# Sheet1-nano.net
KiCad netlist of a schematic drawn in Altium Designer
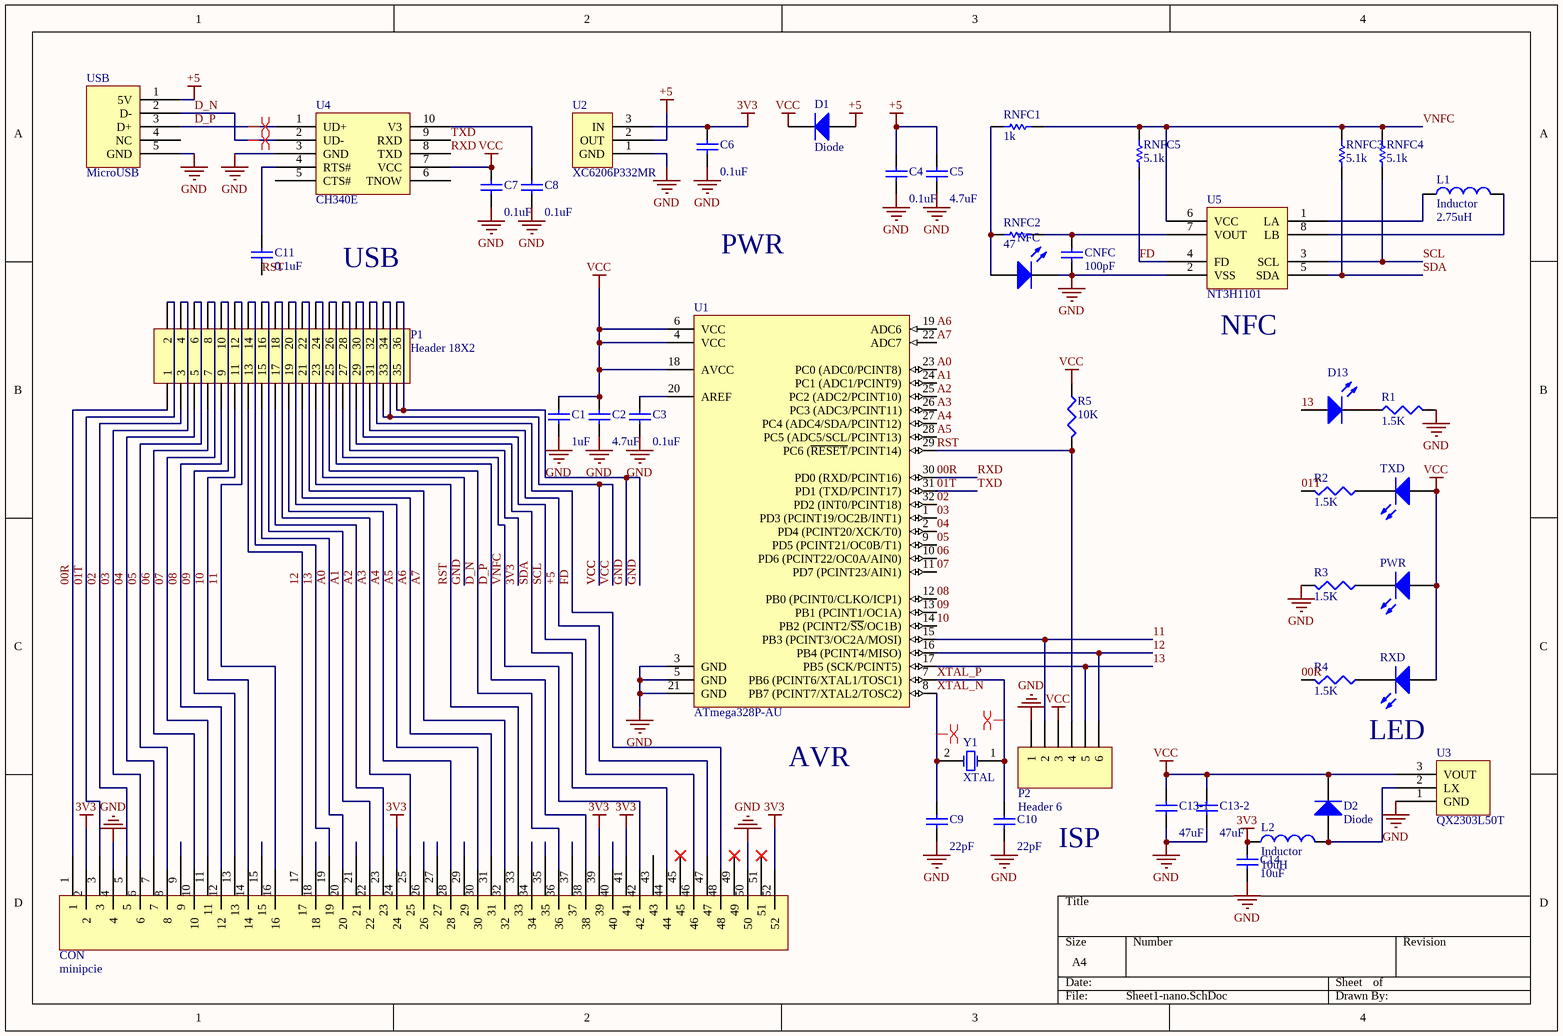
[diagram p0: Sheet1-nano.SchDoc]

(export (version "E")
  (design (tool "Eeschema 10.0.6"))
  (components
    (comp (ref "C1")
      (value "1uF")
      (footprint "0603C")
      (description "Capacitor")
      (fields (field (name "Comment") "Cap") (field (name "PUBLISHER") "Altium Limited"))
      (libsource (lib "Miscellaneous Devices") (part "Cap"))
    )
    (comp (ref "C2")
      (value "4.7uF")
      (footprint "0603C")
      (description "Capacitor")
      (fields (field (name "Comment") "Cap") (field (name "PUBLISHER") "Altium Limited"))
      (libsource (lib "Miscellaneous Devices") (part "Cap"))
    )
    (comp (ref "C3")
      (value "0.1uF")
      (footprint "0603C")
      (description "Capacitor")
      (fields (field (name "Comment") "Cap") (field (name "PUBLISHER") "Altium Limited"))
      (libsource (lib "Miscellaneous Devices") (part "Cap"))
    )
    (comp (ref "C4")
      (value "0.1uF")
      (footprint "0603C")
      (description "Capacitor")
      (fields (field (name "Comment") "Cap") (field (name "PUBLISHER") "Altium Limited"))
      (libsource (lib "Miscellaneous Devices") (part "Cap"))
    )
    (comp (ref "C5")
      (value "4.7uF")
      (footprint "0603C")
      (description "Capacitor")
      (fields (field (name "Comment") "Cap") (field (name "PUBLISHER") "Altium Limited"))
      (libsource (lib "Miscellaneous Devices") (part "Cap"))
    )
    (comp (ref "C6")
      (value "0.1uF")
      (footprint "0603C")
      (description "Capacitor")
      (fields (field (name "Comment") "Cap") (field (name "PUBLISHER") "Altium Limited"))
      (libsource (lib "Miscellaneous Devices") (part "Cap"))
    )
    (comp (ref "C7")
      (value "0.1uF")
      (footprint "0603C")
      (description "Capacitor")
      (fields (field (name "Comment") "Cap") (field (name "PUBLISHER") "Altium Limited"))
      (libsource (lib "Miscellaneous Devices") (part "Cap"))
    )
    (comp (ref "C8")
      (value "0.1uF")
      (footprint "0603C")
      (description "Capacitor")
      (fields (field (name "Comment") "Cap") (field (name "PUBLISHER") "Altium Limited"))
      (libsource (lib "Miscellaneous Devices") (part "Cap"))
    )
    (comp (ref "C9")
      (value "22pF")
      (footprint "0603C")
      (description "Capacitor")
      (fields (field (name "Comment") "Cap") (field (name "PUBLISHER") "Altium Limited"))
      (libsource (lib "Miscellaneous Devices") (part "Cap"))
    )
    (comp (ref "C10")
      (value "22pF")
      (footprint "0603C")
      (description "Capacitor")
      (fields (field (name "Comment") "Cap") (field (name "PUBLISHER") "Altium Limited"))
      (libsource (lib "Miscellaneous Devices") (part "Cap"))
    )
    (comp (ref "C11")
      (value "0.1uF")
      (footprint "0603C")
      (description "Capacitor")
      (fields (field (name "Comment") "Cap") (field (name "PUBLISHER") "Altium Limited"))
      (libsource (lib "Miscellaneous Devices") (part "Cap"))
    )
    (comp (ref "C13-1")
      (value "47uF")
      (footprint "0603C")
      (description "Capacitor")
      (fields (field (name "Comment") "Cap") (field (name "PUBLISHER") "Altium Limited"))
      (libsource (lib "Miscellaneous Devices") (part "Cap"))
    )
    (comp (ref "C13-2")
      (value "47uF")
      (footprint "0603C")
      (description "Capacitor")
      (fields (field (name "Comment") "Cap") (field (name "PUBLISHER") "Altium Limited"))
      (libsource (lib "Miscellaneous Devices") (part "Cap"))
    )
    (comp (ref "C14")
      (value "10uF")
      (footprint "0603C")
      (description "Capacitor")
      (fields (field (name "Comment") "Cap") (field (name "PUBLISHER") "Altium Limited"))
      (libsource (lib "Miscellaneous Devices") (part "Cap"))
    )
    (comp (ref "CNFC")
      (value "100pF")
      (footprint "0603C")
      (description "Capacitor")
      (fields (field (name "Comment") "Cap") (field (name "PUBLISHER") "Altium Limited"))
      (libsource (lib "Miscellaneous Devices") (part "Cap"))
    )
    (comp (ref "CON")
      (value "minipcie")
      (footprint "MINI PCI E PADS")
      (libsource (lib "Custom") (part "minipcie"))
    )
    (comp (ref "D1")
      (value "Diode")
      (footprint "1206Led")
      (description "Default Diode")
      (fields (field (name "PUBLISHER") "Altium Limited"))
      (libsource (lib "Miscellaneous Devices") (part "Diode"))
    )
    (comp (ref "D2")
      (value "Diode")
      (footprint "1206Led")
      (description "Default Diode")
      (fields (field (name "PUBLISHER") "Altium Limited"))
      (libsource (lib "Miscellaneous Devices") (part "Diode"))
    )
    (comp (ref "D13")
      (value "LED0")
      (footprint "24LIB 3D pcbModel :0805LED2")
      (description "Typical INFRARED GaAs LED")
      (fields (field (name "PUBLISHER") "Altium Limited"))
      (libsource (lib "Miscellaneous Devices") (part "LED0"))
    )
    (comp (ref "L1")
      (value "Inductor")
      (footprint "L-2.75uH")
      (fields (field (name "ALTIUM_VALUE") "2.75uH") (field (name "PUBLISHER") "Altium Limited"))
      (libsource (lib "Miscellaneous Devices") (part "Inductor"))
    )
    (comp (ref "L2")
      (value "Inductor")
      (footprint "0603c")
      (fields (field (name "ALTIUM_VALUE") "10uH") (field (name "PUBLISHER") "Altium Limited"))
      (libsource (lib "Miscellaneous Devices") (part "Inductor"))
    )
    (comp (ref "NFC")
      (value "LED1")
      (footprint "0805LED2")
      (description "Typical RED GaAs LED")
      (fields (field (name "PUBLISHER") "Altium Limited"))
      (libsource (lib "Miscellaneous Devices") (part "LED1"))
    )
    (comp (ref "P1")
      (value "Header 18X2")
      (footprint "HDR2X18")
      (description "Header, 18-Pin, Dual row")
      (fields (field (name "PUBLISHER") "Altium Limited"))
      (libsource (lib "Miscellaneous Connectors") (part "Header 18X2"))
    )
    (comp (ref "P2")
      (value "Header 6")
      (footprint "HDR1X6")
      (description "Header, 6-Pin")
      (fields (field (name "PUBLISHER") "Altium Limited"))
      (libsource (lib "Miscellaneous Connectors") (part "Header 6"))
    )
    (comp (ref "PWR")
      (value "LED0")
      (footprint "24LIB 3D pcbModel :0805LED2")
      (description "Typical INFRARED GaAs LED")
      (fields (field (name "PUBLISHER") "Altium Limited"))
      (libsource (lib "Miscellaneous Devices") (part "LED0"))
    )
    (comp (ref "R1")
      (value "1.5K")
      (footprint "0805-1R")
      (description "Resistor")
      (fields (field (name "Comment") "Res3") (field (name "PUBLISHER") "Altium Limited"))
      (libsource (lib "Miscellaneous Devices") (part "Res3"))
    )
    (comp (ref "R2")
      (value "1.5K")
      (footprint "0805-1R")
      (description "Resistor")
      (fields (field (name "Comment") "Res3") (field (name "PUBLISHER") "Altium Limited"))
      (libsource (lib "Miscellaneous Devices") (part "Res3"))
    )
    (comp (ref "R3")
      (value "1.5K")
      (footprint "0805-1R")
      (description "Resistor")
      (fields (field (name "Comment") "Res3") (field (name "PUBLISHER") "Altium Limited"))
      (libsource (lib "Miscellaneous Devices") (part "Res3"))
    )
    (comp (ref "R4")
      (value "1.5K")
      (footprint "0805-1R")
      (description "Resistor")
      (fields (field (name "Comment") "Res3") (field (name "PUBLISHER") "Altium Limited"))
      (libsource (lib "Miscellaneous Devices") (part "Res3"))
    )
    (comp (ref "R5")
      (value "10K")
      (footprint "0805-1R")
      (description "Resistor")
      (fields (field (name "Comment") "Res3") (field (name "PUBLISHER") "Altium Limited"))
      (libsource (lib "Miscellaneous Devices") (part "Res3"))
    )
    (comp (ref "RNFC1")
      (value "1k")
      (footprint "0805-1R")
      (description "Resistor")
      (fields (field (name "Comment") "Res1") (field (name "PUBLISHER") "Altium Limited"))
      (libsource (lib "Miscellaneous Devices") (part "Res1"))
    )
    (comp (ref "RNFC2")
      (value "47")
      (footprint "0805-1R")
      (description "Resistor")
      (fields (field (name "Comment") "Res1") (field (name "PUBLISHER") "Altium Limited"))
      (libsource (lib "Miscellaneous Devices") (part "Res1"))
    )
    (comp (ref "RNFC3")
      (value "5.1k")
      (footprint "0805-1R")
      (description "Resistor")
      (fields (field (name "Comment") "Res1") (field (name "PUBLISHER") "Altium Limited"))
      (libsource (lib "Miscellaneous Devices") (part "Res1"))
    )
    (comp (ref "RNFC4")
      (value "5.1k")
      (footprint "0805-1R")
      (description "Resistor")
      (fields (field (name "Comment") "Res1") (field (name "PUBLISHER") "Altium Limited"))
      (libsource (lib "Miscellaneous Devices") (part "Res1"))
    )
    (comp (ref "RNFC5")
      (value "5.1k")
      (footprint "0805-1R")
      (description "Resistor")
      (fields (field (name "Comment") "Res1") (field (name "PUBLISHER") "Altium Limited"))
      (libsource (lib "Miscellaneous Devices") (part "Res1"))
    )
    (comp (ref "RXD")
      (value "LED0")
      (footprint "24LIB 3D pcbModel :0805LED2")
      (description "Typical INFRARED GaAs LED")
      (fields (field (name "PUBLISHER") "Altium Limited"))
      (libsource (lib "Miscellaneous Devices") (part "LED0"))
    )
    (comp (ref "TXD")
      (value "LED0")
      (footprint "24LIB 3D pcbModel :0805LED2")
      (description "Typical INFRARED GaAs LED")
      (fields (field (name "PUBLISHER") "Altium Limited"))
      (libsource (lib "Miscellaneous Devices") (part "LED0"))
    )
    (comp (ref "U1")
      (value "ATmega328P-AU")
      (footprint "32A_N")
      (fields (field (name "PUBLISHER") "Altium Limited"))
      (libsource (lib "Atmel Microcontroller 8-Bit megaAVR") (part "ATmega328P-AU"))
    )
    (comp (ref "U2") (value "XC6206P332MR") (footprint "SOT-23") (libsource (lib "Custom") (part "AMS1117")))
    (comp (ref "U3") (value "QX2303L50T") (footprint "sot23") (libsource (lib "Custom") (part "QX2303L50T")))
    (comp (ref "U4") (value "CH340E") (footprint "MS10") (libsource (lib "Custom") (part "CH340E")))
    (comp (ref "U5")
      (value "NT3H1101")
      (footprint "XQFN-8_L1.6-W1.6-P0.50-BL")
      (libsource (lib "IDCARD") (part "NT3H1101"))
    )
    (comp (ref "USB")
      (value "MicroUSB")
      (footprint "MicroUSB-InBoard")
      (libsource (lib "Custom") (part "MicroUSB"))
    )
    (comp (ref "Y1")
      (value "XTAL")
      (footprint "SMD-3225")
      (description "Crystal Oscillator")
      (fields (field (name "PUBLISHER") "Altium Limited"))
      (libsource (lib "Miscellaneous Devices") (part "XTAL"))
    )
  )
  (nets
    (net (code "1") (name "+5") (class "Default")
      (node (ref "C4") (pin "2") (pinfunction "2_2") (pintype "passive"))
      (node (ref "C5") (pin "2") (pinfunction "2_2") (pintype "passive"))
      (node (ref "CON") (pin "47") (pinfunction "47_47") (pintype "passive"))
      (node (ref "D1") (pin "1") (pinfunction "A_1") (pintype "passive"))
      (node (ref "P1") (pin "31") (pinfunction "31_31") (pintype "passive"))
      (node (ref "U2") (pin "2") (pinfunction "OUT_2") (pintype "passive"))
      (node (ref "USB") (pin "1") (pinfunction "5V_1") (pintype "passive"))
    )
    (net (code "2") (name "/00R") (class "Default")
      (node (ref "CON") (pin "1") (pinfunction "1_1") (pintype "passive"))
      (node (ref "P1") (pin "1") (pinfunction "1_1") (pintype "passive"))
      (node (ref "R4") (pin "2") (pinfunction "2_2") (pintype "passive"))
      (node (ref "U1") (pin "30") (pinfunction "PD0_(RXD/PCINT16)_30") (pintype "bidirectional"))
      (node (ref "U4") (pin "8") (pinfunction "TXD_8") (pintype "passive"))
    )
    (net (code "3") (name "/01T") (class "Default")
      (node (ref "CON") (pin "3") (pinfunction "3_3") (pintype "passive"))
      (node (ref "P1") (pin "2") (pinfunction "2_2") (pintype "passive"))
      (node (ref "R2") (pin "2") (pinfunction "2_2") (pintype "passive"))
      (node (ref "U1") (pin "31") (pinfunction "PD1_(TXD/PCINT17)_31") (pintype "bidirectional"))
      (node (ref "U4") (pin "9") (pinfunction "RXD_9") (pintype "passive"))
    )
    (net (code "4") (name "/02") (class "Default")
      (node (ref "CON") (pin "5") (pinfunction "5_5") (pintype "passive"))
      (node (ref "P1") (pin "3") (pinfunction "3_3") (pintype "passive"))
      (node (ref "U1") (pin "32") (pinfunction "PD2_(INT0/PCINT18)_32") (pintype "bidirectional"))
    )
    (net (code "5") (name "/03") (class "Default")
      (node (ref "CON") (pin "6") (pinfunction "6_6") (pintype "passive"))
      (node (ref "P1") (pin "4") (pinfunction "4_4") (pintype "passive"))
      (node (ref "U1") (pin "1") (pinfunction "PD3_(PCINT19/OC2B/INT1)_1") (pintype "bidirectional"))
    )
    (net (code "6") (name "/04") (class "Default")
      (node (ref "CON") (pin "7") (pinfunction "7_7") (pintype "passive"))
      (node (ref "P1") (pin "5") (pinfunction "5_5") (pintype "passive"))
      (node (ref "U1") (pin "2") (pinfunction "PD4_(PCINT20/XCK/T0)_2") (pintype "bidirectional"))
    )
    (net (code "7") (name "/05") (class "Default")
      (node (ref "CON") (pin "8") (pinfunction "8_8") (pintype "passive"))
      (node (ref "P1") (pin "6") (pinfunction "6_6") (pintype "passive"))
      (node (ref "U1") (pin "9") (pinfunction "PD5_(PCINT21/OC0B/T1)_9") (pintype "bidirectional"))
    )
    (net (code "8") (name "/06") (class "Default")
      (node (ref "CON") (pin "10") (pinfunction "10_10") (pintype "passive"))
      (node (ref "P1") (pin "7") (pinfunction "7_7") (pintype "passive"))
      (node (ref "U1") (pin "10") (pinfunction "PD6_(PCINT22/OC0A/AIN0)_10") (pintype "bidirectional"))
    )
    (net (code "9") (name "/07") (class "Default")
      (node (ref "CON") (pin "11") (pinfunction "11_11") (pintype "passive"))
      (node (ref "P1") (pin "8") (pinfunction "8_8") (pintype "passive"))
      (node (ref "U1") (pin "11") (pinfunction "PD7_(PCINT23/AIN1)_11") (pintype "bidirectional"))
    )
    (net (code "10") (name "/08") (class "Default")
      (node (ref "CON") (pin "12") (pinfunction "12_12") (pintype "passive"))
      (node (ref "P1") (pin "9") (pinfunction "9_9") (pintype "passive"))
      (node (ref "U1") (pin "12") (pinfunction "PB0_(PCINT0/CLKO/ICP1)_12") (pintype "bidirectional"))
    )
    (net (code "11") (name "/09") (class "Default")
      (node (ref "CON") (pin "13") (pinfunction "13_13") (pintype "passive"))
      (node (ref "P1") (pin "10") (pinfunction "10_10") (pintype "passive"))
      (node (ref "U1") (pin "13") (pinfunction "PB1_(PCINT1/OC1A)_13") (pintype "bidirectional"))
    )
    (net (code "12") (name "/10") (class "Default")
      (node (ref "CON") (pin "14") (pinfunction "14_14") (pintype "passive"))
      (node (ref "P1") (pin "11") (pinfunction "11_11") (pintype "passive"))
      (node (ref "U1") (pin "14") (pinfunction "PB2_(PCINT2/~{SS}/OC1B)_14") (pintype "bidirectional"))
    )
    (net (code "13") (name "/11") (class "Default")
      (node (ref "CON") (pin "16") (pinfunction "16_16") (pintype "passive"))
      (node (ref "P1") (pin "12") (pinfunction "12_12") (pintype "passive"))
      (node (ref "P2") (pin "2") (pinfunction "2_2") (pintype "passive"))
      (node (ref "U1") (pin "15") (pinfunction "PB3_(PCINT3/OC2A/MOSI)_15") (pintype "bidirectional"))
    )
    (net (code "14") (name "/12") (class "Default")
      (node (ref "CON") (pin "17") (pinfunction "17_17") (pintype "passive"))
      (node (ref "P1") (pin "13") (pinfunction "13_13") (pintype "passive"))
      (node (ref "P2") (pin "6") (pinfunction "6_6") (pintype "passive"))
      (node (ref "U1") (pin "16") (pinfunction "PB4_(PCINT4/MISO)_16") (pintype "bidirectional"))
    )
    (net (code "15") (name "/13") (class "Default")
      (node (ref "CON") (pin "19") (pinfunction "19_19") (pintype "passive"))
      (node (ref "D13") (pin "1") (pinfunction "A_1") (pintype "passive"))
      (node (ref "P1") (pin "14") (pinfunction "14_14") (pintype "passive"))
      (node (ref "P2") (pin "5") (pinfunction "5_5") (pintype "passive"))
      (node (ref "U1") (pin "17") (pinfunction "PB5_(SCK/PCINT5)_17") (pintype "bidirectional"))
    )
    (net (code "16") (name "/A0") (class "Default")
      (node (ref "CON") (pin "20") (pinfunction "20_20") (pintype "passive"))
      (node (ref "P1") (pin "15") (pinfunction "15_15") (pintype "passive"))
      (node (ref "U1") (pin "23") (pinfunction "PC0_(ADC0/PCINT8)_23") (pintype "bidirectional"))
    )
    (net (code "17") (name "/A1") (class "Default")
      (node (ref "CON") (pin "22") (pinfunction "22_22") (pintype "passive"))
      (node (ref "P1") (pin "16") (pinfunction "16_16") (pintype "passive"))
      (node (ref "U1") (pin "24") (pinfunction "PC1_(ADC1/PCINT9)_24") (pintype "bidirectional"))
    )
    (net (code "18") (name "/A2") (class "Default")
      (node (ref "CON") (pin "23") (pinfunction "23_23") (pintype "passive"))
      (node (ref "P1") (pin "17") (pinfunction "17_17") (pintype "passive"))
      (node (ref "U1") (pin "25") (pinfunction "PC2_(ADC2/PCINT10)_25") (pintype "bidirectional"))
    )
    (net (code "19") (name "/A3") (class "Default")
      (node (ref "CON") (pin "25") (pinfunction "25_25") (pintype "passive"))
      (node (ref "P1") (pin "18") (pinfunction "18_18") (pintype "passive"))
      (node (ref "U1") (pin "26") (pinfunction "PC3_(ADC3/PCINT11)_26") (pintype "bidirectional"))
    )
    (net (code "20") (name "/A4") (class "Default")
      (node (ref "CON") (pin "28") (pinfunction "28_28") (pintype "passive"))
      (node (ref "P1") (pin "19") (pinfunction "19_19") (pintype "passive"))
      (node (ref "U1") (pin "27") (pinfunction "PC4_(ADC4/SDA/PCINT12)_27") (pintype "bidirectional"))
    )
    (net (code "21") (name "/A5") (class "Default")
      (node (ref "CON") (pin "30") (pinfunction "30_30") (pintype "passive"))
      (node (ref "P1") (pin "20") (pinfunction "20_20") (pintype "passive"))
      (node (ref "U1") (pin "28") (pinfunction "PC5_(ADC5/SCL/PCINT13)_28") (pintype "bidirectional"))
    )
    (net (code "22") (name "/A6") (class "Default")
      (node (ref "CON") (pin "31") (pinfunction "31_31") (pintype "passive"))
      (node (ref "P1") (pin "21") (pinfunction "21_21") (pintype "passive"))
      (node (ref "U1") (pin "19") (pinfunction "ADC6_19") (pintype "input"))
    )
    (net (code "23") (name "/A7") (class "Default")
      (node (ref "CON") (pin "32") (pinfunction "32_32") (pintype "passive"))
      (node (ref "P1") (pin "22") (pinfunction "22_22") (pintype "passive"))
      (node (ref "U1") (pin "22") (pinfunction "ADC7_22") (pintype "input"))
    )
    (net (code "24") (name "/D_N") (class "Default")
      (node (ref "CON") (pin "36") (pinfunction "36_36") (pintype "passive"))
      (node (ref "P1") (pin "25") (pinfunction "25_25") (pintype "passive"))
      (node (ref "U4") (pin "2") (pinfunction "UD-_2") (pintype "passive"))
      (node (ref "USB") (pin "2") (pinfunction "D-_2") (pintype "passive"))
    )
    (net (code "25") (name "/D_P") (class "Default")
      (node (ref "CON") (pin "38") (pinfunction "38_38") (pintype "passive"))
      (node (ref "P1") (pin "26") (pinfunction "26_26") (pintype "passive"))
      (node (ref "U4") (pin "1") (pinfunction "UD+_1") (pintype "passive"))
      (node (ref "USB") (pin "3") (pinfunction "D+_3") (pintype "passive"))
    )
    (net (code "26") (name "/FD") (class "Default")
      (node (ref "CON") (pin "48") (pinfunction "48_48") (pintype "passive"))
      (node (ref "P1") (pin "32") (pinfunction "32_32") (pintype "passive"))
      (node (ref "RNFC5") (pin "1") (pinfunction "1_1") (pintype "passive"))
      (node (ref "U5") (pin "4") (pinfunction "FD_4") (pintype "passive"))
    )
    (net (code "27") (name "/RST") (class "Default")
      (node (ref "C11") (pin "1") (pinfunction "1_1") (pintype "passive"))
      (node (ref "CON") (pin "33") (pinfunction "33_33") (pintype "passive"))
      (node (ref "P1") (pin "23") (pinfunction "23_23") (pintype "passive"))
      (node (ref "P2") (pin "4") (pinfunction "4_4") (pintype "passive"))
      (node (ref "R5") (pin "2") (pinfunction "2_2") (pintype "passive"))
      (node (ref "U1") (pin "29") (pinfunction "PC6_(~{RESET}/PCINT14)_29") (pintype "bidirectional"))
    )
    (net (code "28") (name "/SCL") (class "Default")
      (node (ref "CON") (pin "46") (pinfunction "46_46") (pintype "passive"))
      (node (ref "P1") (pin "30") (pinfunction "30_30") (pintype "passive"))
      (node (ref "RNFC4") (pin "1") (pinfunction "1_1") (pintype "passive"))
      (node (ref "U5") (pin "3") (pinfunction "SCL_3") (pintype "passive"))
    )
    (net (code "29") (name "/SDA") (class "Default")
      (node (ref "CON") (pin "44") (pinfunction "44_44") (pintype "passive"))
      (node (ref "P1") (pin "29") (pinfunction "29_29") (pintype "passive"))
      (node (ref "RNFC3") (pin "1") (pinfunction "1_1") (pintype "passive"))
      (node (ref "U5") (pin "5") (pinfunction "SDA_5") (pintype "passive"))
    )
    (net (code "30") (name "/VNFC") (class "Default")
      (node (ref "CON") (pin "42") (pinfunction "42_42") (pintype "passive"))
      (node (ref "P1") (pin "27") (pinfunction "27_27") (pintype "passive"))
      (node (ref "RNFC1") (pin "2") (pinfunction "2_2") (pintype "passive"))
      (node (ref "RNFC3") (pin "2") (pinfunction "2_2") (pintype "passive"))
      (node (ref "RNFC4") (pin "2") (pinfunction "2_2") (pintype "passive"))
      (node (ref "RNFC5") (pin "2") (pinfunction "2_2") (pintype "passive"))
      (node (ref "U5") (pin "6") (pinfunction "VCC_6") (pintype "passive"))
    )
    (net (code "31") (name "/XTAL_N") (class "Default")
      (node (ref "C9") (pin "2") (pinfunction "2_2") (pintype "passive"))
      (node (ref "U1") (pin "8") (pinfunction "PB7_(PCINT7/XTAL2/TOSC2)_8") (pintype "bidirectional"))
      (node (ref "Y1") (pin "2") (pinfunction "OSC2_2") (pintype "passive"))
    )
    (net (code "32") (name "/XTAL_P") (class "Default")
      (node (ref "C10") (pin "2") (pinfunction "2_2") (pintype "passive"))
      (node (ref "U1") (pin "7") (pinfunction "PB6_(PCINT6/XTAL1/TOSC1)_7") (pintype "bidirectional"))
      (node (ref "Y1") (pin "1") (pinfunction "OSC1_1") (pintype "passive"))
    )
    (net (code "33") (name "3V3") (class "Default")
      (node (ref "C14") (pin "1") (pinfunction "1_1") (pintype "passive"))
      (node (ref "C6") (pin "2") (pinfunction "2_2") (pintype "passive"))
      (node (ref "CON") (pin "2") (pinfunction "2_2") (pintype "passive"))
      (node (ref "CON") (pin "24") (pinfunction "24_24") (pintype "passive"))
      (node (ref "CON") (pin "39") (pinfunction "39_39") (pintype "passive"))
      (node (ref "CON") (pin "41") (pinfunction "41_41") (pintype "passive"))
      (node (ref "CON") (pin "52") (pinfunction "52_52") (pintype "passive"))
      (node (ref "L2") (pin "1") (pinfunction "1_1") (pintype "passive"))
      (node (ref "P1") (pin "28") (pinfunction "28_28") (pintype "passive"))
      (node (ref "U2") (pin "3") (pinfunction "IN_3") (pintype "passive"))
    )
    (net (code "34") (name "GND") (class "Default")
      (node (ref "C1") (pin "1") (pinfunction "1_1") (pintype "passive"))
      (node (ref "C10") (pin "1") (pinfunction "1_1") (pintype "passive"))
      (node (ref "C13-1") (pin "1") (pinfunction "1_1") (pintype "passive"))
      (node (ref "C13-2") (pin "1") (pinfunction "1_1") (pintype "passive"))
      (node (ref "C14") (pin "2") (pinfunction "2_2") (pintype "passive"))
      (node (ref "C2") (pin "1") (pinfunction "1_1") (pintype "passive"))
      (node (ref "C3") (pin "1") (pinfunction "1_1") (pintype "passive"))
      (node (ref "C4") (pin "1") (pinfunction "1_1") (pintype "passive"))
      (node (ref "C5") (pin "1") (pinfunction "1_1") (pintype "passive"))
      (node (ref "C6") (pin "1") (pinfunction "1_1") (pintype "passive"))
      (node (ref "C7") (pin "1") (pinfunction "1_1") (pintype "passive"))
      (node (ref "C8") (pin "1") (pinfunction "1_1") (pintype "passive"))
      (node (ref "C9") (pin "1") (pinfunction "1_1") (pintype "passive"))
      (node (ref "CNFC") (pin "1") (pinfunction "1_1") (pintype "passive"))
      (node (ref "CON") (pin "4") (pinfunction "4_4") (pintype "passive"))
      (node (ref "CON") (pin "50") (pinfunction "50_50") (pintype "passive"))
      (node (ref "NFC") (pin "2") (pinfunction "K_2") (pintype "passive"))
      (node (ref "P1") (pin "24") (pinfunction "24_24") (pintype "passive"))
      (node (ref "P1") (pin "35") (pinfunction "35_35") (pintype "passive"))
      (node (ref "P1") (pin "36") (pinfunction "36_36") (pintype "passive"))
      (node (ref "P2") (pin "1") (pinfunction "1_1") (pintype "passive"))
      (node (ref "R1") (pin "2") (pinfunction "2_2") (pintype "passive"))
      (node (ref "R3") (pin "2") (pinfunction "2_2") (pintype "passive"))
      (node (ref "U1") (pin "21") (pinfunction "GND_21") (pintype "power_in"))
      (node (ref "U1") (pin "3") (pinfunction "GND_3") (pintype "power_in"))
      (node (ref "U1") (pin "5") (pinfunction "GND_5") (pintype "power_in"))
      (node (ref "U2") (pin "1") (pinfunction "GND_1") (pintype "passive"))
      (node (ref "U3") (pin "1") (pinfunction "GND_1") (pintype "passive"))
      (node (ref "U4") (pin "3") (pinfunction "GND_3") (pintype "passive"))
      (node (ref "U5") (pin "2") (pinfunction "VSS_2") (pintype "passive"))
      (node (ref "USB") (pin "5") (pinfunction "GND_5") (pintype "passive"))
    )
    (net (code "35") (name "Net-(D2-A)") (class "Default")
      (node (ref "D2") (pin "1") (pinfunction "A_1") (pintype "passive"))
      (node (ref "L2") (pin "2") (pinfunction "2_2") (pintype "passive"))
      (node (ref "U3") (pin "2") (pinfunction "LX_2") (pintype "passive"))
    )
    (net (code "36") (name "Net-(D13-K)") (class "Default")
      (node (ref "D13") (pin "2") (pinfunction "K_2") (pintype "passive"))
      (node (ref "R1") (pin "1") (pinfunction "1_1") (pintype "passive"))
    )
    (net (code "37") (name "Net-(NFC-A)") (class "Default")
      (node (ref "NFC") (pin "1") (pinfunction "A_1") (pintype "passive"))
      (node (ref "RNFC1") (pin "1") (pinfunction "1_1") (pintype "passive"))
      (node (ref "RNFC2") (pin "1") (pinfunction "1_1") (pintype "passive"))
    )
    (net (code "38") (name "Net-(PWR-K)") (class "Default")
      (node (ref "PWR") (pin "2") (pinfunction "K_2") (pintype "passive"))
      (node (ref "R3") (pin "1") (pinfunction "1_1") (pintype "passive"))
    )
    (net (code "39") (name "Net-(RXD-K)") (class "Default")
      (node (ref "R4") (pin "1") (pinfunction "1_1") (pintype "passive"))
      (node (ref "RXD") (pin "2") (pinfunction "K_2") (pintype "passive"))
    )
    (net (code "40") (name "Net-(TXD-K)") (class "Default")
      (node (ref "R2") (pin "1") (pinfunction "1_1") (pintype "passive"))
      (node (ref "TXD") (pin "2") (pinfunction "K_2") (pintype "passive"))
    )
    (net (code "41") (name "Net-(U1-AREF)") (class "Default")
      (node (ref "C3") (pin "2") (pinfunction "2_2") (pintype "passive"))
      (node (ref "U1") (pin "20") (pinfunction "AREF_20") (pintype "passive"))
    )
    (net (code "42") (name "Net-(U4-RTS#)") (class "Default")
      (node (ref "C11") (pin "2") (pinfunction "2_2") (pintype "passive"))
      (node (ref "U4") (pin "4") (pinfunction "RTS#_4") (pintype "passive"))
    )
    (net (code "43") (name "Net-(U4-V3)") (class "Default")
      (node (ref "C8") (pin "2") (pinfunction "2_2") (pintype "passive"))
      (node (ref "U4") (pin "10") (pinfunction "V3_10") (pintype "passive"))
    )
    (net (code "44") (name "Net-(U5-LA)") (class "Default")
      (node (ref "L1") (pin "1") (pinfunction "1_1") (pintype "passive"))
      (node (ref "U5") (pin "1") (pinfunction "LA_1") (pintype "passive"))
    )
    (net (code "45") (name "Net-(U5-LB)") (class "Default")
      (node (ref "L1") (pin "2") (pinfunction "2_2") (pintype "passive"))
      (node (ref "U5") (pin "8") (pinfunction "LB_8") (pintype "passive"))
    )
    (net (code "46") (name "Net-(U5-VOUT)") (class "Default")
      (node (ref "CNFC") (pin "2") (pinfunction "2_2") (pintype "passive"))
      (node (ref "RNFC2") (pin "2") (pinfunction "2_2") (pintype "passive"))
      (node (ref "U5") (pin "7") (pinfunction "VOUT_7") (pintype "passive"))
    )
    (net (code "47") (name "VCC") (class "Default")
      (node (ref "C1") (pin "2") (pinfunction "2_2") (pintype "passive"))
      (node (ref "C13-1") (pin "2") (pinfunction "2_2") (pintype "passive"))
      (node (ref "C13-2") (pin "2") (pinfunction "2_2") (pintype "passive"))
      (node (ref "C2") (pin "2") (pinfunction "2_2") (pintype "passive"))
      (node (ref "C7") (pin "2") (pinfunction "2_2") (pintype "passive"))
      (node (ref "D1") (pin "2") (pinfunction "K_2") (pintype "passive"))
      (node (ref "D2") (pin "2") (pinfunction "K_2") (pintype "passive"))
      (node (ref "P1") (pin "33") (pinfunction "33_33") (pintype "passive"))
      (node (ref "P1") (pin "34") (pinfunction "34_34") (pintype "passive"))
      (node (ref "P2") (pin "3") (pinfunction "3_3") (pintype "passive"))
      (node (ref "PWR") (pin "1") (pinfunction "A_1") (pintype "passive"))
      (node (ref "R5") (pin "1") (pinfunction "1_1") (pintype "passive"))
      (node (ref "RXD") (pin "1") (pinfunction "A_1") (pintype "passive"))
      (node (ref "TXD") (pin "1") (pinfunction "A_1") (pintype "passive"))
      (node (ref "U1") (pin "18") (pinfunction "AVCC_18") (pintype "power_in"))
      (node (ref "U1") (pin "4") (pinfunction "VCC_4") (pintype "power_in"))
      (node (ref "U1") (pin "6") (pinfunction "VCC_6") (pintype "power_in"))
      (node (ref "U3") (pin "3") (pinfunction "VOUT_3") (pintype "passive"))
      (node (ref "U4") (pin "7") (pinfunction "VCC_7") (pintype "passive"))
    )
    (net (code "48") (name "unconnected-(CON-Pad9)") (class "Default")
      (node (ref "CON") (pin "9") (pinfunction "9_9") (pintype "passive"))
    )
    (net (code "49") (name "unconnected-(CON-Pad15)") (class "Default")
      (node (ref "CON") (pin "15") (pinfunction "15_15") (pintype "passive"))
    )
    (net (code "50") (name "unconnected-(CON-Pad18)") (class "Default")
      (node (ref "CON") (pin "18") (pinfunction "18_18") (pintype "passive"))
    )
    (net (code "51") (name "unconnected-(CON-Pad21)") (class "Default")
      (node (ref "CON") (pin "21") (pinfunction "21_21") (pintype "passive"))
    )
    (net (code "52") (name "unconnected-(CON-Pad26)") (class "Default")
      (node (ref "CON") (pin "26") (pinfunction "26_26") (pintype "passive"))
    )
    (net (code "53") (name "unconnected-(CON-Pad27)") (class "Default")
      (node (ref "CON") (pin "27") (pinfunction "27_27") (pintype "passive"))
    )
    (net (code "54") (name "unconnected-(CON-Pad29)") (class "Default")
      (node (ref "CON") (pin "29") (pinfunction "29_29") (pintype "passive"))
    )
    (net (code "55") (name "unconnected-(CON-Pad34)") (class "Default")
      (node (ref "CON") (pin "34") (pinfunction "34_34") (pintype "passive"))
    )
    (net (code "56") (name "unconnected-(CON-Pad35)") (class "Default")
      (node (ref "CON") (pin "35") (pinfunction "35_35") (pintype "passive"))
    )
    (net (code "57") (name "unconnected-(CON-Pad37)") (class "Default")
      (node (ref "CON") (pin "37") (pinfunction "37_37") (pintype "passive"))
    )
    (net (code "58") (name "unconnected-(CON-Pad40)") (class "Default")
      (node (ref "CON") (pin "40") (pinfunction "40_40") (pintype "passive"))
    )
    (net (code "59") (name "unconnected-(CON-Pad43)") (class "Default")
      (node (ref "CON") (pin "43") (pinfunction "43_43") (pintype "passive"))
    )
    (net (code "60") (name "unconnected-(CON-Pad45)") (class "Default")
      (node (ref "CON") (pin "45") (pinfunction "45_45") (pintype "passive+no_connect"))
    )
    (net (code "61") (name "unconnected-(CON-Pad49)") (class "Default")
      (node (ref "CON") (pin "49") (pinfunction "49_49") (pintype "passive+no_connect"))
    )
    (net (code "62") (name "unconnected-(CON-Pad51)") (class "Default")
      (node (ref "CON") (pin "51") (pinfunction "51_51") (pintype "passive+no_connect"))
    )
    (net (code "63") (name "unconnected-(U4-CTS#-Pad5)") (class "Default")
      (node (ref "U4") (pin "5") (pinfunction "CTS#_5") (pintype "passive"))
    )
    (net (code "64") (name "unconnected-(U4-TNOW-Pad6)") (class "Default")
      (node (ref "U4") (pin "6") (pinfunction "TNOW_6") (pintype "passive"))
    )
    (net (code "65") (name "unconnected-(USB-NC-Pad4)") (class "Default")
      (node (ref "USB") (pin "4") (pinfunction "NC_4") (pintype "passive"))
    )
  )
)
